# electrical_diagram.net
KiCad netlist of a schematic drawn in EAGLE
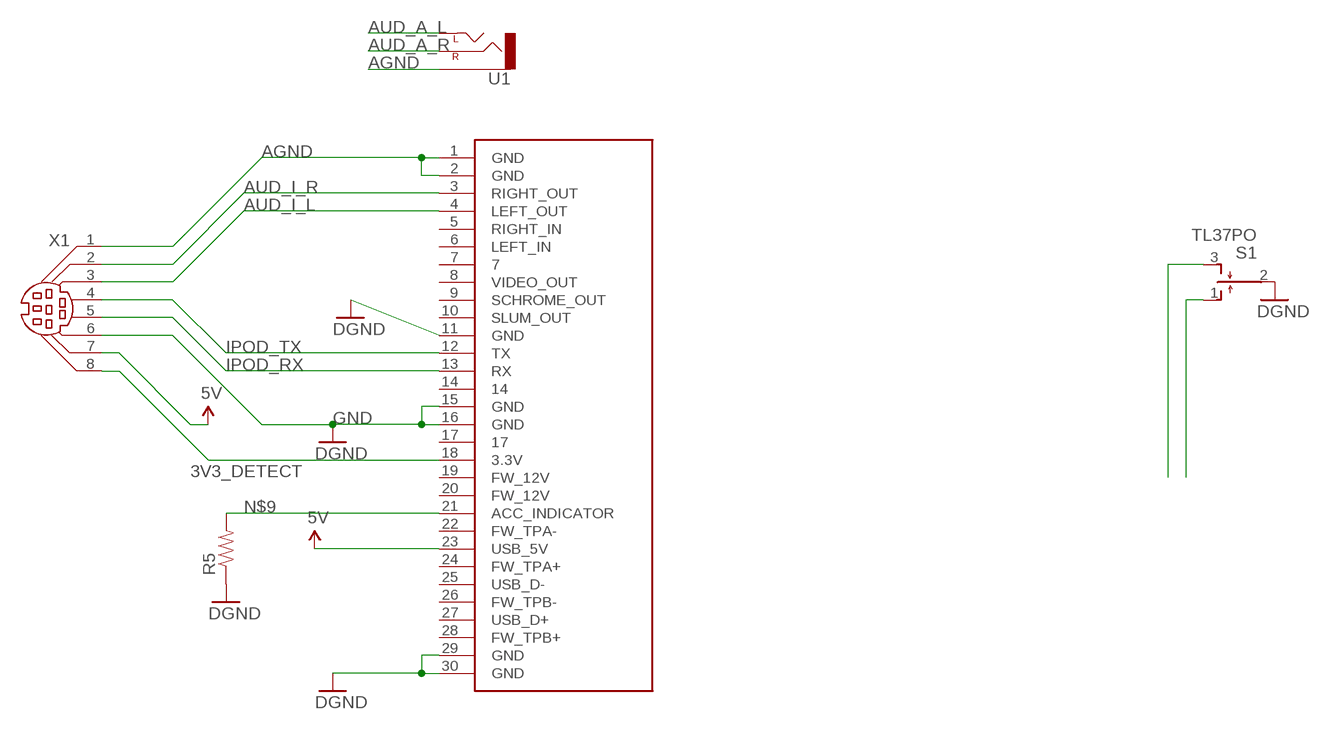
[diagram p0: schematic, sheet 1]

(export (version "E")
  (design (tool "Eeschema 10.0.6"))
  (components
    (comp (ref "R5")
      (value "RESISTOR0805-RES")
      (footprint "eagle-import:0805")
      (libsource (lib "eagle-import") (part "RESISTOR0805-RES"))
    )
    (comp (ref "S1")
      (value "TL37PO")
      (footprint "eagle-import:TL3XPO")
      (libsource (lib "eagle-import") (part "TL37PO"))
    )
    (comp (ref "U$1")
      (value "IPOD_CONNECTOR_MALE")
      (footprint "eagle-import:IPOD_MALE_CONNECTOR")
      (libsource (lib "eagle-import") (part "IPOD_CONNECTOR_MALE"))
    )
    (comp (ref "U1")
      (value "AUDIO-JACKSMD2")
      (footprint "eagle-import:AUDIO-JACK-3.5MM-SMD")
      (libsource (lib "eagle-import") (part "AUDIO-JACKSMD2"))
    )
    (comp (ref "X1")
      (value "MDIN08K")
      (footprint "eagle-import:MDIN08K")
      (libsource (lib "eagle-import") (part "MDIN08K"))
    )
  )
  (nets
    (net (code "1") (name "/3V3_DETECT") (class "Default")
      (node (ref "U$1") (pin "18") (pinfunction "3.3V_18") (pintype "bidirectional"))
      (node (ref "X1") (pin "8") (pinfunction "8_8") (pintype "passive"))
    )
    (net (code "2") (name "/AGND") (class "Default")
      (node (ref "U$1") (pin "1") (pinfunction "GND_1") (pintype "bidirectional"))
      (node (ref "U$1") (pin "2") (pinfunction "GND_2") (pintype "bidirectional"))
      (node (ref "U1") (pin "SLEEVE") (pinfunction "SLEEVE_SLEEVE") (pintype "bidirectional"))
      (node (ref "X1") (pin "1") (pinfunction "1_1") (pintype "passive"))
    )
    (net (code "3") (name "/AUD_A_L") (class "Default")
      (node (ref "U1") (pin "TIP") (pinfunction "LEFT_TIP") (pintype "bidirectional"))
    )
    (net (code "4") (name "/AUD_A_R") (class "Default")
      (node (ref "U1") (pin "RING") (pinfunction "RIGHT_RING") (pintype "bidirectional"))
    )
    (net (code "5") (name "/AUD_I_L") (class "Default")
      (node (ref "U$1") (pin "4") (pinfunction "LEFT_OUT_4") (pintype "bidirectional"))
      (node (ref "X1") (pin "3") (pinfunction "3_3") (pintype "passive"))
    )
    (net (code "6") (name "/AUD_I_R") (class "Default")
      (node (ref "U$1") (pin "3") (pinfunction "RIGHT_OUT_3") (pintype "bidirectional"))
      (node (ref "X1") (pin "2") (pinfunction "2_2") (pintype "passive"))
    )
    (net (code "7") (name "/IPOD_RX") (class "Default")
      (node (ref "U$1") (pin "13") (pinfunction "RX_13") (pintype "bidirectional"))
      (node (ref "X1") (pin "5") (pinfunction "5_5") (pintype "passive"))
    )
    (net (code "8") (name "/IPOD_TX") (class "Default")
      (node (ref "U$1") (pin "12") (pinfunction "TX_12") (pintype "bidirectional"))
      (node (ref "X1") (pin "4") (pinfunction "4_4") (pintype "passive"))
    )
    (net (code "9") (name "/N$9") (class "Default")
      (node (ref "R5") (pin "2") (pinfunction "2_2") (pintype "passive"))
      (node (ref "U$1") (pin "21") (pinfunction "ACC_INDICATOR_21") (pintype "bidirectional"))
    )
    (net (code "10") (name "5V") (class "Default")
      (node (ref "U$1") (pin "23") (pinfunction "USB_5V_23") (pintype "bidirectional"))
      (node (ref "X1") (pin "7") (pinfunction "7_7") (pintype "passive"))
    )
    (net (code "11") (name "DGND") (class "Default")
      (node (ref "R5") (pin "1") (pinfunction "1_1") (pintype "passive"))
      (node (ref "S1") (pin "2") (pinfunction "P_2") (pintype "passive"))
      (node (ref "U$1") (pin "11") (pinfunction "GND_11") (pintype "bidirectional"))
      (node (ref "U$1") (pin "15") (pinfunction "GND_15") (pintype "bidirectional"))
      (node (ref "U$1") (pin "16") (pinfunction "GND_16") (pintype "bidirectional"))
      (node (ref "U$1") (pin "29") (pinfunction "GND_29") (pintype "bidirectional"))
      (node (ref "U$1") (pin "30") (pinfunction "GND_30") (pintype "bidirectional"))
      (node (ref "X1") (pin "6") (pinfunction "6_6") (pintype "passive"))
    )
    (net (code "12") (name "unconnected-(S1-O-Pad1)") (class "Default")
      (node (ref "S1") (pin "1") (pinfunction "O_1") (pintype "passive"))
    )
    (net (code "13") (name "unconnected-(S1-S-Pad3)") (class "Default")
      (node (ref "S1") (pin "3") (pinfunction "S_3") (pintype "passive"))
    )
    (net (code "14") (name "unconnected-(U$1-FW_12V-Pad19)") (class "Default")
      (node (ref "U$1") (pin "19") (pinfunction "FW_12V_19") (pintype "bidirectional"))
    )
    (net (code "15") (name "unconnected-(U$1-FW_12V-Pad20)") (class "Default")
      (node (ref "U$1") (pin "20") (pinfunction "FW_12V_20") (pintype "bidirectional"))
    )
    (net (code "16") (name "unconnected-(U$1-FW_TPA+-Pad24)") (class "Default")
      (node (ref "U$1") (pin "24") (pinfunction "FW_TPA+_24") (pintype "bidirectional"))
    )
    (net (code "17") (name "unconnected-(U$1-FW_TPA--Pad22)") (class "Default")
      (node (ref "U$1") (pin "22") (pinfunction "FW_TPA-_22") (pintype "bidirectional"))
    )
    (net (code "18") (name "unconnected-(U$1-FW_TPB+-Pad28)") (class "Default")
      (node (ref "U$1") (pin "28") (pinfunction "FW_TPB+_28") (pintype "bidirectional"))
    )
    (net (code "19") (name "unconnected-(U$1-FW_TPB--Pad26)") (class "Default")
      (node (ref "U$1") (pin "26") (pinfunction "FW_TPB-_26") (pintype "bidirectional"))
    )
    (net (code "20") (name "unconnected-(U$1-LEFT_IN-Pad6)") (class "Default")
      (node (ref "U$1") (pin "6") (pinfunction "LEFT_IN_6") (pintype "bidirectional"))
    )
    (net (code "21") (name "unconnected-(U$1-Pad7)") (class "Default")
      (node (ref "U$1") (pin "7") (pinfunction "7_7") (pintype "bidirectional"))
    )
    (net (code "22") (name "unconnected-(U$1-Pad14)") (class "Default")
      (node (ref "U$1") (pin "14") (pinfunction "14_14") (pintype "bidirectional"))
    )
    (net (code "23") (name "unconnected-(U$1-Pad17)") (class "Default")
      (node (ref "U$1") (pin "17") (pinfunction "17_17") (pintype "bidirectional"))
    )
    (net (code "24") (name "unconnected-(U$1-RIGHT_IN-Pad5)") (class "Default")
      (node (ref "U$1") (pin "5") (pinfunction "RIGHT_IN_5") (pintype "bidirectional"))
    )
    (net (code "25") (name "unconnected-(U$1-SCHROME_OUT-Pad9)") (class "Default")
      (node (ref "U$1") (pin "9") (pinfunction "SCHROME_OUT_9") (pintype "bidirectional"))
    )
    (net (code "26") (name "unconnected-(U$1-SLUM_OUT-Pad10)") (class "Default")
      (node (ref "U$1") (pin "10") (pinfunction "SLUM_OUT_10") (pintype "bidirectional"))
    )
    (net (code "27") (name "unconnected-(U$1-USB_D+-Pad27)") (class "Default")
      (node (ref "U$1") (pin "27") (pinfunction "USB_D+_27") (pintype "bidirectional"))
    )
    (net (code "28") (name "unconnected-(U$1-USB_D--Pad25)") (class "Default")
      (node (ref "U$1") (pin "25") (pinfunction "USB_D-_25") (pintype "bidirectional"))
    )
    (net (code "29") (name "unconnected-(U$1-VIDEO_OUT-Pad8)") (class "Default")
      (node (ref "U$1") (pin "8") (pinfunction "VIDEO_OUT_8") (pintype "bidirectional"))
    )
  )
)
